# Controller_page.net
KiCad netlist of a schematic drawn in Altium Designer
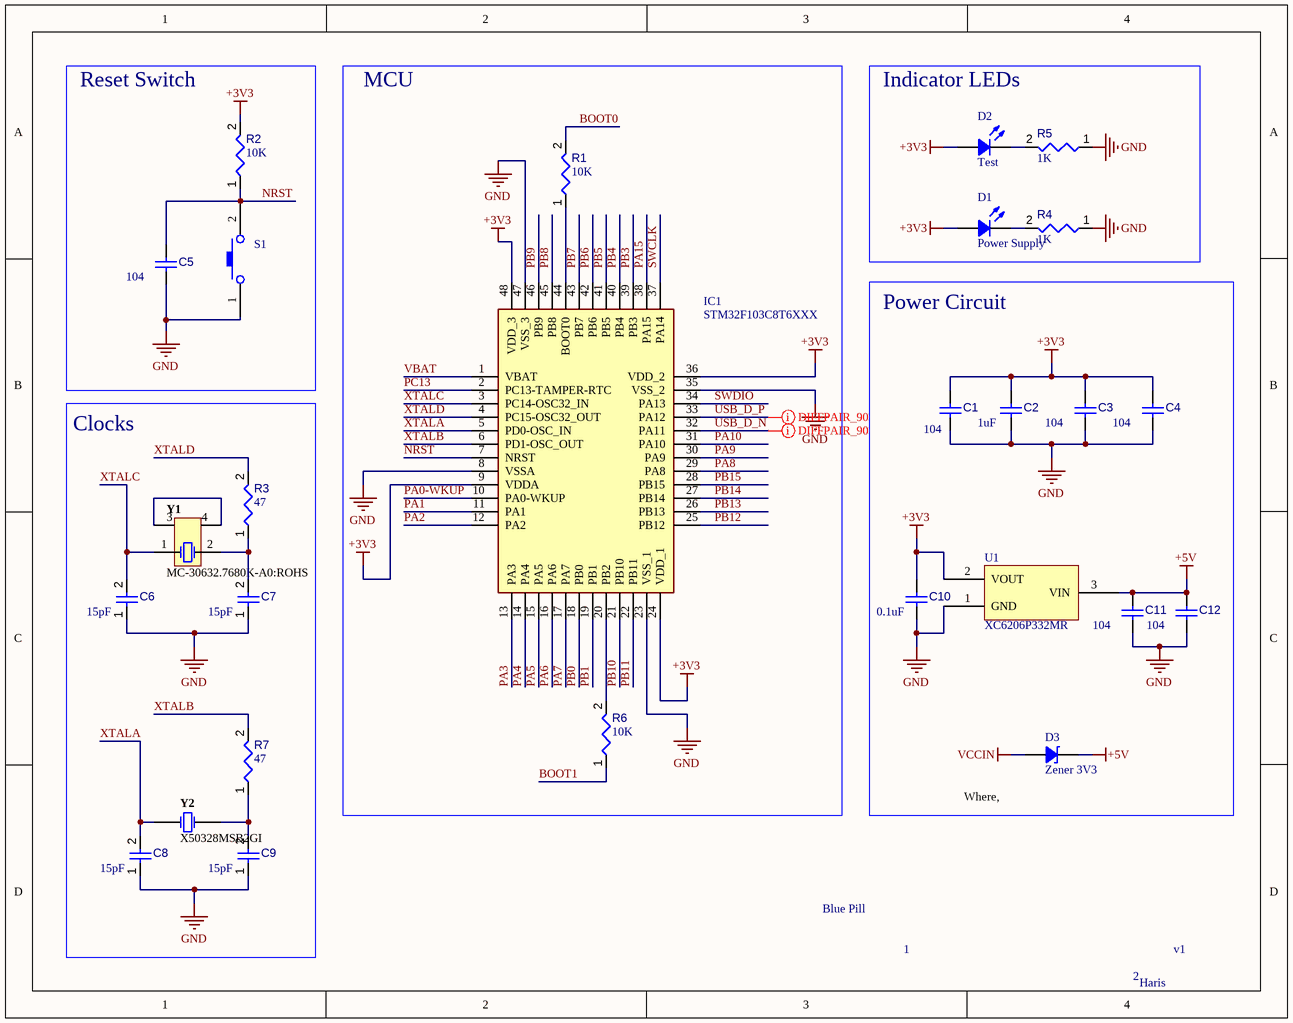
[diagram p0: Controller_page.SchDoc]

(export (version "E")
  (design (tool "Eeschema 10.0.6"))
  (components
    (comp (ref "C1")
      (value "104")
      (footprint "CAPC0805(2012)145_L")
      (description "Chip Capacitor, 4.7µF +/-40%, 25V, 0805, Thickness 1.45 mm")
      (fields (field (name "TOLERANCE") "20%") (field (name "Comment") "Capacitor 4.7µF +/-40% 25V 0805"))
      (libsource (lib "Universität Siegen") (part "CAP-NP-2"))
    )
    (comp (ref "C2")
      (value "1uF")
      (footprint "CAPC0805(2012)145_L")
      (description "Chip Capacitor, 4.7µF +/-40%, 25V, 0805, Thickness 1.45 mm")
      (fields (field (name "TOLERANCE") "20%") (field (name "Comment") "Capacitor 4.7µF +/-40% 25V 0805"))
      (libsource (lib "Universität Siegen") (part "CAP-NP-2"))
    )
    (comp (ref "C3")
      (value "104")
      (footprint "CAPC0805(2012)145_L")
      (description "Chip Capacitor, 4.7µF +/-40%, 25V, 0805, Thickness 1.45 mm")
      (fields (field (name "TOLERANCE") "20%") (field (name "Comment") "Capacitor 4.7µF +/-40% 25V 0805"))
      (libsource (lib "Universität Siegen") (part "CAP-NP-2"))
    )
    (comp (ref "C4")
      (value "104")
      (footprint "CAPC0805(2012)145_L")
      (description "Chip Capacitor, 4.7µF +/-40%, 25V, 0805, Thickness 1.45 mm")
      (fields (field (name "TOLERANCE") "20%") (field (name "Comment") "Capacitor 4.7µF +/-40% 25V 0805"))
      (libsource (lib "Universität Siegen") (part "CAP-NP-2"))
    )
    (comp (ref "C5")
      (value "104")
      (footprint "CAPC0805(2012)145_L")
      (description "Chip Capacitor, 4.7µF +/-40%, 25V, 0805, Thickness 1.45 mm")
      (fields (field (name "TOLERANCE") "20%") (field (name "Comment") "Capacitor 4.7µF +/-40% 25V 0805"))
      (libsource (lib "Universität Siegen") (part "CAP-NP-2"))
    )
    (comp (ref "C6")
      (value "15pF")
      (footprint "CAPC0805(2012)145_L")
      (description "Chip Capacitor, 4.7µF +/-40%, 25V, 0805, Thickness 1.45 mm")
      (fields (field (name "TOLERANCE") "20%") (field (name "Comment") "Capacitor 4.7µF +/-40% 25V 0805"))
      (libsource (lib "") (part "CAP-NP-2_1"))
    )
    (comp (ref "C7")
      (value "15pF")
      (footprint "CAPC0805(2012)145_L")
      (description "Chip Capacitor, 4.7µF +/-40%, 25V, 0805, Thickness 1.45 mm")
      (fields (field (name "TOLERANCE") "20%") (field (name "Comment") "Capacitor 4.7µF +/-40% 25V 0805"))
      (libsource (lib "") (part "CAP-NP-2_1"))
    )
    (comp (ref "C8")
      (value "15pF")
      (footprint "CAPC0805(2012)145_L")
      (description "Chip Capacitor, 4.7µF +/-40%, 25V, 0805, Thickness 1.45 mm")
      (fields (field (name "TOLERANCE") "20%") (field (name "Comment") "Capacitor 4.7µF +/-40% 25V 0805"))
      (libsource (lib "") (part "CAP-NP-2_1"))
    )
    (comp (ref "C9")
      (value "15pF")
      (footprint "CAPC0805(2012)145_L")
      (description "Chip Capacitor, 4.7µF +/-40%, 25V, 0805, Thickness 1.45 mm")
      (fields (field (name "TOLERANCE") "20%") (field (name "Comment") "Capacitor 4.7µF +/-40% 25V 0805"))
      (libsource (lib "") (part "CAP-NP-2_1"))
    )
    (comp (ref "C10")
      (value "0.1uF")
      (footprint "CAPC0805(2012)145_L")
      (description "Chip Capacitor, 4.7µF +/-40%, 25V, 0805, Thickness 1.45 mm")
      (fields (field (name "TOLERANCE") "20%") (field (name "Comment") "Capacitor 4.7µF +/-40% 25V 0805"))
      (libsource (lib "Universität Siegen") (part "CAP-NP-2"))
    )
    (comp (ref "C11")
      (value "104")
      (footprint "CAPC0805(2012)145_L")
      (description "Chip Capacitor, 4.7µF +/-40%, 25V, 0805, Thickness 1.45 mm")
      (fields (field (name "TOLERANCE") "20%") (field (name "Comment") "Capacitor 4.7µF +/-40% 25V 0805"))
      (libsource (lib "Universität Siegen") (part "CAP-NP-2"))
    )
    (comp (ref "C12")
      (value "104")
      (footprint "CAPC0805(2012)145_L")
      (description "Chip Capacitor, 4.7µF +/-40%, 25V, 0805, Thickness 1.45 mm")
      (fields (field (name "TOLERANCE") "20%") (field (name "Comment") "Capacitor 4.7µF +/-40% 25V 0805"))
      (libsource (lib "Universität Siegen") (part "CAP-NP-2"))
    )
    (comp (ref "D1")
      (value "Power Supply")
      (footprint "LED 0805_2012 GREEN")
      (description "LED GREEN CLEAR CHIP SMD")
      (fields (field (name "PART NUMBER") "APHCM2012CGCK-F01") (field (name "MANUFACTURER") "Kingbright"))
      (libsource (lib "Celestial Altium Library - altium_library") (part "LED"))
    )
    (comp (ref "D2")
      (value "Test")
      (footprint "LED 0805_2012 RED")
      (description "LED RED CLEAR SMD")
      (fields (field (name "PART NUMBER") "LTST-C170KAKT") (field (name "MANUFACTURER") "Lite-On Inc."))
      (libsource (lib "Celestial Altium Library - altium_library") (part "LED"))
    )
    (comp (ref "D3")
      (value "Zener 3V3")
      (footprint "SOD-123")
      (description "DIODE ZENER 3.3V 410MW SOD123")
      (fields
        (field (name "PART NUMBER") "BZT52C3V3-HE3-18")
        (field (name "MANUFACTURER") "Vishay Semiconductor Diodes Division")
      )
      (libsource (lib "Celestial Altium Library - altium_library") (part "Diode Zener"))
    )
    (comp (ref "IC1")
      (value "STM32F103C8T6XXX")
      (footprint "SamacSys:QFP50P900X900X160-48N")
      (description "Integrated Circuit")
      (libsource (lib "*") (part "STM32F103C8T6XXX"))
    )
    (comp (ref "R1")
      (value "10K")
      (footprint "RESC0805(2012)_L")
      (description "470R 0.125W 5% 0805 (2012 Metric)  SMD")
      (fields (field (name "POWER") "125mW") (field (name "TOLERANCE") "5%"))
      (libsource (lib "Universität Siegen") (part "470R5J"))
    )
    (comp (ref "R2")
      (value "10K")
      (footprint "RESC0805(2012)_L")
      (description "470R 0.125W 5% 0805 (2012 Metric)  SMD")
      (fields (field (name "POWER") "125mW") (field (name "TOLERANCE") "5%"))
      (libsource (lib "Universität Siegen") (part "470R5J"))
    )
    (comp (ref "R3")
      (value "47")
      (footprint "RESC0805(2012)_L")
      (description "470R 0.125W 5% 0805 (2012 Metric)  SMD")
      (fields (field (name "POWER") "125mW") (field (name "TOLERANCE") "5%"))
      (libsource (lib "Universität Siegen") (part "470R5J"))
    )
    (comp (ref "R4")
      (value "1K")
      (footprint "RESC0805(2012)_L")
      (description "470R 0.125W 5% 0805 (2012 Metric)  SMD")
      (fields (field (name "POWER") "125mW") (field (name "TOLERANCE") "5%"))
      (libsource (lib "Universität Siegen") (part "470R5J"))
    )
    (comp (ref "R5")
      (value "1K")
      (footprint "RESC0805(2012)_L")
      (description "470R 0.125W 5% 0805 (2012 Metric)  SMD")
      (fields (field (name "POWER") "125mW") (field (name "TOLERANCE") "5%"))
      (libsource (lib "Universität Siegen") (part "470R5J"))
    )
    (comp (ref "R6")
      (value "10K")
      (footprint "RESC0805(2012)_L")
      (description "470R 0.125W 5% 0805 (2012 Metric)  SMD")
      (fields (field (name "POWER") "125mW") (field (name "TOLERANCE") "5%"))
      (libsource (lib "Universität Siegen") (part "470R5J"))
    )
    (comp (ref "R7")
      (value "47")
      (footprint "RESC0805(2012)_L")
      (description "470R 0.125W 5% 0805 (2012 Metric)  SMD")
      (fields (field (name "POWER") "125mW") (field (name "TOLERANCE") "5%"))
      (libsource (lib "Universität Siegen") (part "470R5J"))
    )
    (comp (ref "S1")
      (value "TS-1088-AR02016")
      (footprint "TS-1088-AR02016-Footprint-1")
      (description "NO 50mA 100MΩ 100000 Times 12V 160gf@±50gf Brick nogging SPST SMD Tactile Switches ROHS")
      (libsource (lib "Universität Siegen") (part "TS-1088-AR02016-Symbol-1"))
    )
    (comp (ref "U1")
      (value "XC6206P332MR")
      (footprint "XC6206P332MR-Footprint-1")
      (description "200mA Fixed 3.3V Positive 6V SOT-23-3L Linear Voltage Regulators (LDO) ROHS")
      (libsource (lib "Universität Siegen") (part "XC6206P332MR"))
    )
    (comp (ref "Y1")
      (value "MC-30632.7680K-A0:ROHS")
      (footprint "MC-30632.7680K-A0:ROHS-Footprint-1")
      (description "32.768 kHz ±20ppm Crystal 12.5pF 50 kOhms 4-SOJ, 5.50mm pitch")
      (libsource (lib "Universität Siegen") (part "XTAL-4"))
    )
    (comp (ref "Y2")
      (value "X50328MSB2GI")
      (footprint "X50328MSB2GI-Footprint-1")
      (description "8MHz 20pF ±10ppm SMD5032-2P Crystals ROHS")
      (libsource (lib "Universität Siegen") (part "XTAL-2"))
    )
  )
  (nets
    (net (code "1") (name "+3V3") (class "Default")
      (node (ref "C1") (pin "2") (pinfunction "2_2") (pintype "passive"))
      (node (ref "C10") (pin "2") (pinfunction "2_2") (pintype "passive"))
      (node (ref "C2") (pin "2") (pinfunction "2_2") (pintype "passive"))
      (node (ref "C3") (pin "2") (pinfunction "2_2") (pintype "passive"))
      (node (ref "C4") (pin "2") (pinfunction "2_2") (pintype "passive"))
      (node (ref "D1") (pin "1") (pinfunction "1_1") (pintype "passive"))
      (node (ref "D2") (pin "1") (pinfunction "1_1") (pintype "passive"))
      (node (ref "IC1") (pin "24") (pinfunction "VDD_1_24") (pintype "passive"))
      (node (ref "IC1") (pin "36") (pinfunction "VDD_2_36") (pintype "passive"))
      (node (ref "IC1") (pin "48") (pinfunction "VDD_3_48") (pintype "passive"))
      (node (ref "IC1") (pin "9") (pinfunction "VDDA_9") (pintype "passive"))
      (node (ref "R2") (pin "2") (pinfunction "2_2") (pintype "passive"))
      (node (ref "U1") (pin "2") (pinfunction "VOUT_2") (pintype "passive"))
    )
    (net (code "2") (name "+5V") (class "Default")
      (node (ref "C11") (pin "2") (pinfunction "2_2") (pintype "passive"))
      (node (ref "C12") (pin "2") (pinfunction "2_2") (pintype "passive"))
      (node (ref "D3") (pin "2") (pinfunction "2_2") (pintype "passive"))
      (node (ref "U1") (pin "3") (pinfunction "VIN_3") (pintype "passive"))
    )
    (net (code "3") (name "/BOOT0") (class "Default")
      (node (ref "R1") (pin "2") (pinfunction "2_2") (pintype "passive"))
    )
    (net (code "4") (name "/BOOT1") (class "Default")
      (node (ref "R6") (pin "1") (pinfunction "1_1") (pintype "passive"))
    )
    (net (code "5") (name "/NRST") (class "Default")
      (node (ref "C5") (pin "2") (pinfunction "2_2") (pintype "passive"))
      (node (ref "IC1") (pin "7") (pinfunction "NRST_7") (pintype "passive"))
      (node (ref "R2") (pin "1") (pinfunction "1_1") (pintype "passive"))
      (node (ref "S1") (pin "2") (pinfunction "2_2") (pintype "passive"))
    )
    (net (code "6") (name "/PA0-WKUP") (class "Default")
      (node (ref "IC1") (pin "10") (pinfunction "PA0-WKUP_10") (pintype "passive"))
    )
    (net (code "7") (name "/PA1") (class "Default")
      (node (ref "IC1") (pin "11") (pinfunction "PA1_11") (pintype "passive"))
    )
    (net (code "8") (name "/PA2") (class "Default")
      (node (ref "IC1") (pin "12") (pinfunction "PA2_12") (pintype "passive"))
    )
    (net (code "9") (name "/PA3") (class "Default")
      (node (ref "IC1") (pin "13") (pinfunction "PA3_13") (pintype "passive"))
    )
    (net (code "10") (name "/PA4") (class "Default")
      (node (ref "IC1") (pin "14") (pinfunction "PA4_14") (pintype "passive"))
    )
    (net (code "11") (name "/PA5") (class "Default")
      (node (ref "IC1") (pin "15") (pinfunction "PA5_15") (pintype "passive"))
    )
    (net (code "12") (name "/PA6") (class "Default")
      (node (ref "IC1") (pin "16") (pinfunction "PA6_16") (pintype "passive"))
    )
    (net (code "13") (name "/PA7") (class "Default")
      (node (ref "IC1") (pin "17") (pinfunction "PA7_17") (pintype "passive"))
    )
    (net (code "14") (name "/PA8") (class "Default")
      (node (ref "IC1") (pin "29") (pinfunction "PA8_29") (pintype "passive"))
    )
    (net (code "15") (name "/PA9") (class "Default")
      (node (ref "IC1") (pin "30") (pinfunction "PA9_30") (pintype "passive"))
    )
    (net (code "16") (name "/PA10") (class "Default")
      (node (ref "IC1") (pin "31") (pinfunction "PA10_31") (pintype "passive"))
    )
    (net (code "17") (name "/PA15") (class "Default")
      (node (ref "IC1") (pin "38") (pinfunction "PA15_38") (pintype "passive"))
    )
    (net (code "18") (name "/PB0") (class "Default")
      (node (ref "IC1") (pin "18") (pinfunction "PB0_18") (pintype "passive"))
    )
    (net (code "19") (name "/PB1") (class "Default")
      (node (ref "IC1") (pin "19") (pinfunction "PB1_19") (pintype "passive"))
    )
    (net (code "20") (name "/PB3") (class "Default")
      (node (ref "IC1") (pin "39") (pinfunction "PB3_39") (pintype "passive"))
    )
    (net (code "21") (name "/PB4") (class "Default")
      (node (ref "IC1") (pin "40") (pinfunction "PB4_40") (pintype "passive"))
    )
    (net (code "22") (name "/PB5") (class "Default")
      (node (ref "IC1") (pin "41") (pinfunction "PB5_41") (pintype "passive"))
    )
    (net (code "23") (name "/PB6") (class "Default")
      (node (ref "IC1") (pin "42") (pinfunction "PB6_42") (pintype "passive"))
    )
    (net (code "24") (name "/PB7") (class "Default")
      (node (ref "IC1") (pin "43") (pinfunction "PB7_43") (pintype "passive"))
    )
    (net (code "25") (name "/PB8") (class "Default")
      (node (ref "IC1") (pin "45") (pinfunction "PB8_45") (pintype "passive"))
    )
    (net (code "26") (name "/PB9") (class "Default")
      (node (ref "IC1") (pin "46") (pinfunction "PB9_46") (pintype "passive"))
    )
    (net (code "27") (name "/PB10") (class "Default")
      (node (ref "IC1") (pin "21") (pinfunction "PB10_21") (pintype "passive"))
    )
    (net (code "28") (name "/PB11") (class "Default")
      (node (ref "IC1") (pin "22") (pinfunction "PB11_22") (pintype "passive"))
    )
    (net (code "29") (name "/PB12") (class "Default")
      (node (ref "IC1") (pin "25") (pinfunction "PB12_25") (pintype "passive"))
    )
    (net (code "30") (name "/PB13") (class "Default")
      (node (ref "IC1") (pin "26") (pinfunction "PB13_26") (pintype "passive"))
    )
    (net (code "31") (name "/PB14") (class "Default")
      (node (ref "IC1") (pin "27") (pinfunction "PB14_27") (pintype "passive"))
    )
    (net (code "32") (name "/PB15") (class "Default")
      (node (ref "IC1") (pin "28") (pinfunction "PB15_28") (pintype "passive"))
    )
    (net (code "33") (name "/PC13") (class "Default")
      (node (ref "IC1") (pin "2") (pinfunction "PC13-TAMPER-RTC_2") (pintype "passive"))
    )
    (net (code "34") (name "/SWCLK") (class "Default")
      (node (ref "IC1") (pin "37") (pinfunction "PA14_37") (pintype "passive"))
    )
    (net (code "35") (name "/SWDIO") (class "Default")
      (node (ref "IC1") (pin "34") (pinfunction "PA13_34") (pintype "passive"))
    )
    (net (code "36") (name "/USB_D_N") (class "Default")
      (node (ref "IC1") (pin "32") (pinfunction "PA11_32") (pintype "passive"))
    )
    (net (code "37") (name "/USB_D_P") (class "Default")
      (node (ref "IC1") (pin "33") (pinfunction "PA12_33") (pintype "passive"))
    )
    (net (code "38") (name "/VBAT") (class "Default")
      (node (ref "IC1") (pin "1") (pinfunction "VBAT_1") (pintype "passive"))
    )
    (net (code "39") (name "/XTALA") (class "Default")
      (node (ref "C8") (pin "2") (pinfunction "2_2") (pintype "passive"))
      (node (ref "IC1") (pin "5") (pinfunction "PD0-OSC_IN_5") (pintype "passive"))
      (node (ref "Y2") (pin "1") (pinfunction "1_1") (pintype "passive"))
    )
    (net (code "40") (name "/XTALB") (class "Default")
      (node (ref "IC1") (pin "6") (pinfunction "PD1-OSC_OUT_6") (pintype "passive"))
      (node (ref "R7") (pin "2") (pinfunction "2_2") (pintype "passive"))
    )
    (net (code "41") (name "/XTALC") (class "Default")
      (node (ref "C6") (pin "2") (pinfunction "2_2") (pintype "passive"))
      (node (ref "IC1") (pin "3") (pinfunction "PC14-OSC32_IN_3") (pintype "passive"))
      (node (ref "Y1") (pin "1") (pinfunction "1_1") (pintype "passive"))
    )
    (net (code "42") (name "/XTALD") (class "Default")
      (node (ref "IC1") (pin "4") (pinfunction "PC15-OSC32_OUT_4") (pintype "passive"))
      (node (ref "R3") (pin "2") (pinfunction "2_2") (pintype "passive"))
    )
    (net (code "43") (name "GND") (class "Default")
      (node (ref "C1") (pin "1") (pinfunction "1_1") (pintype "passive"))
      (node (ref "C10") (pin "1") (pinfunction "1_1") (pintype "passive"))
      (node (ref "C11") (pin "1") (pinfunction "1_1") (pintype "passive"))
      (node (ref "C12") (pin "1") (pinfunction "1_1") (pintype "passive"))
      (node (ref "C2") (pin "1") (pinfunction "1_1") (pintype "passive"))
      (node (ref "C3") (pin "1") (pinfunction "1_1") (pintype "passive"))
      (node (ref "C4") (pin "1") (pinfunction "1_1") (pintype "passive"))
      (node (ref "C5") (pin "1") (pinfunction "1_1") (pintype "passive"))
      (node (ref "C6") (pin "1") (pinfunction "1_1") (pintype "passive"))
      (node (ref "C7") (pin "1") (pinfunction "1_1") (pintype "passive"))
      (node (ref "C8") (pin "1") (pinfunction "1_1") (pintype "passive"))
      (node (ref "C9") (pin "1") (pinfunction "1_1") (pintype "passive"))
      (node (ref "IC1") (pin "23") (pinfunction "VSS_1_23") (pintype "passive"))
      (node (ref "IC1") (pin "35") (pinfunction "VSS_2_35") (pintype "passive"))
      (node (ref "IC1") (pin "47") (pinfunction "VSS_3_47") (pintype "passive"))
      (node (ref "IC1") (pin "8") (pinfunction "VSSA_8") (pintype "passive"))
      (node (ref "R4") (pin "1") (pinfunction "1_1") (pintype "passive"))
      (node (ref "R5") (pin "1") (pinfunction "1_1") (pintype "passive"))
      (node (ref "S1") (pin "1") (pinfunction "1_1") (pintype "passive"))
      (node (ref "U1") (pin "1") (pinfunction "GND_1") (pintype "passive"))
    )
    (net (code "44") (name "Net-(C7-Pad2)") (class "Default")
      (node (ref "C7") (pin "2") (pinfunction "2_2") (pintype "passive"))
      (node (ref "R3") (pin "1") (pinfunction "1_1") (pintype "passive"))
      (node (ref "Y1") (pin "2") (pinfunction "2_2") (pintype "passive"))
    )
    (net (code "45") (name "Net-(C9-Pad2)") (class "Default")
      (node (ref "C9") (pin "2") (pinfunction "2_2") (pintype "passive"))
      (node (ref "R7") (pin "1") (pinfunction "1_1") (pintype "passive"))
      (node (ref "Y2") (pin "2") (pinfunction "2_2") (pintype "passive"))
    )
    (net (code "46") (name "Net-(D1-Pad2)") (class "Default")
      (node (ref "D1") (pin "2") (pinfunction "2_2") (pintype "passive"))
      (node (ref "R4") (pin "2") (pinfunction "2_2") (pintype "passive"))
    )
    (net (code "47") (name "Net-(D2-Pad2)") (class "Default")
      (node (ref "D2") (pin "2") (pinfunction "2_2") (pintype "passive"))
      (node (ref "R5") (pin "2") (pinfunction "2_2") (pintype "passive"))
    )
    (net (code "48") (name "Net-(IC1-BOOT0)") (class "Default")
      (node (ref "IC1") (pin "44") (pinfunction "BOOT0_44") (pintype "passive"))
      (node (ref "R1") (pin "1") (pinfunction "1_1") (pintype "passive"))
    )
    (net (code "49") (name "Net-(IC1-PB2)") (class "Default")
      (node (ref "IC1") (pin "20") (pinfunction "PB2_20") (pintype "passive"))
      (node (ref "R6") (pin "2") (pinfunction "2_2") (pintype "passive"))
    )
    (net (code "50") (name "VCCIN") (class "Default")
      (node (ref "D3") (pin "1") (pinfunction "1_1") (pintype "passive"))
    )
    (net (code "51") (name "unconnected-(Y1-Pad3)") (class "Default")
      (node (ref "Y1") (pin "3") (pinfunction "3_3") (pintype "passive"))
    )
    (net (code "52") (name "unconnected-(Y1-Pad4)") (class "Default")
      (node (ref "Y1") (pin "4") (pinfunction "4_4") (pintype "passive"))
    )
  )
)
